# OmniSensor.net
KiCad netlist of a schematic drawn in Altium Designer
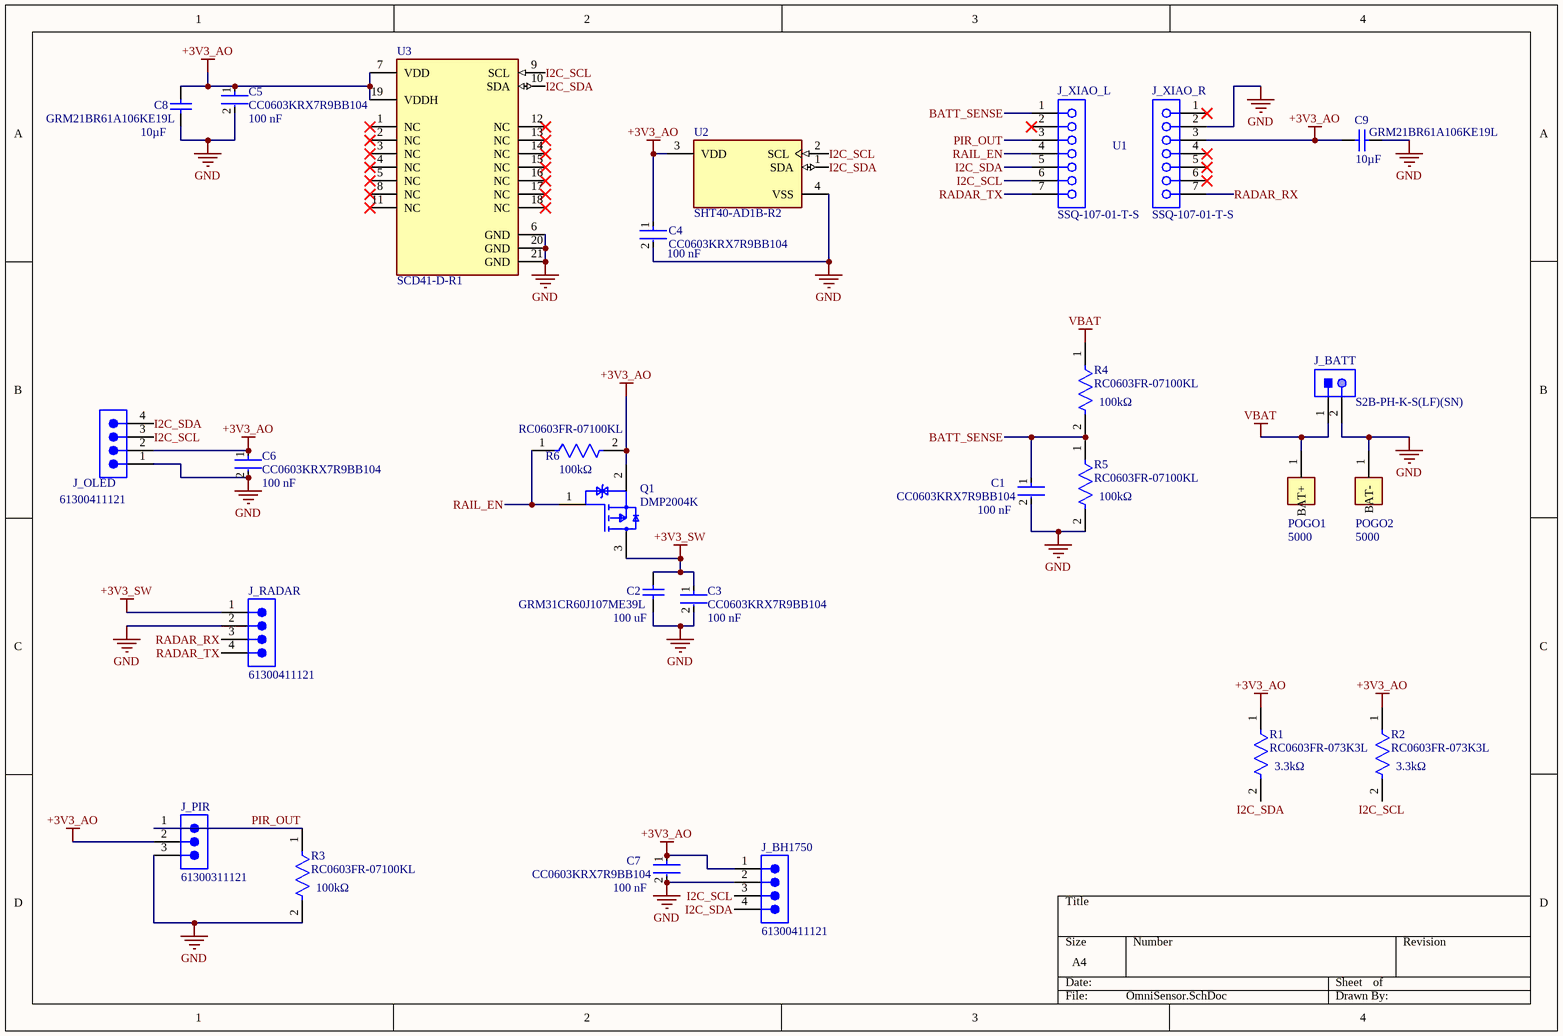
[diagram p0: OmniSensor.SchDoc]

(export (version "E")
  (design (tool "Eeschema 10.0.6"))
  (components
    (comp (ref "C1")
      (value "CC0603KRX7R9BB104")
      (footprint "FP-CC0603-DA-MFG")
      (description "CAP CER 0.1UF 50V X7R 0603")
      (fields
        (field (name "MANUFACTURER") "YAGEO")
        (field (name "VOLTAGE") "50 V")
        (field (name "ALTIUM_VALUE") "100 nF")
      )
      (libsource (lib "Altium Content Vault") (part "11868f565c42a9108669ba33697ecf6"))
    )
    (comp (ref "C2")
      (value "GRM31CR60J107ME39L")
      (footprint "CAPC3216X190X55ML30T25")
      (description "Chip Capacitor, 100 uF, +/- 20%, 6.3 V, -55 to 85 degC, 1206 (3216 Metric), RoHS, Tape and Reel")
      (fields (field (name "TOLERANCE") "20%") (field (name "CAPACITANCE") "100 uF"))
      (libsource (lib "Altium Content Vault") (part "CAP-NP-2"))
    )
    (comp (ref "C3")
      (value "CC0603KRX7R9BB104")
      (footprint "FP-CC0603-DA-MFG")
      (description "CAP CER 0.1UF 50V X7R 0603")
      (fields
        (field (name "MANUFACTURER") "YAGEO")
        (field (name "VOLTAGE") "50 V")
        (field (name "ALTIUM_VALUE") "100 nF")
      )
      (libsource (lib "Altium Content Vault") (part "11868f565c42a9108669ba33697ecf6"))
    )
    (comp (ref "C4")
      (value "CC0603KRX7R9BB104")
      (footprint "FP-CC0603-DA-MFG")
      (description "CAP CER 0.1UF 50V X7R 0603")
      (fields
        (field (name "MANUFACTURER") "YAGEO")
        (field (name "VOLTAGE") "50 V")
        (field (name "CAPACITANCE") "100 nF")
      )
      (libsource (lib "Altium Content Vault") (part "11868f565c42a9108669ba33697ecf6"))
    )
    (comp (ref "C5")
      (value "CC0603KRX7R9BB104")
      (footprint "FP-CC0603-DA-MFG")
      (description "CAP CER 0.1UF 50V X7R 0603")
      (fields
        (field (name "MANUFACTURER") "YAGEO")
        (field (name "VOLTAGE") "50 V")
        (field (name "CAPACITANCE") "100 nF")
      )
      (libsource (lib "Altium Content Vault") (part "11868f565c42a9108669ba33697ecf6"))
    )
    (comp (ref "C6")
      (value "CC0603KRX7R9BB104")
      (footprint "FP-CC0603-DA-MFG")
      (description "CAP CER 0.1UF 50V X7R 0603")
      (fields
        (field (name "MANUFACTURER") "YAGEO")
        (field (name "VOLTAGE") "50 V")
        (field (name "CAPACITANCE") "100 nF")
      )
      (libsource (lib "Altium Content Vault") (part "11868f565c42a9108669ba33697ecf6"))
    )
    (comp (ref "C7")
      (value "CC0603KRX7R9BB104")
      (footprint "FP-CC0603-DA-MFG")
      (description "CAP CER 0.1UF 50V X7R 0603")
      (fields
        (field (name "MANUFACTURER") "YAGEO")
        (field (name "VOLTAGE") "50 V")
        (field (name "CAPACITANCE") "100 nF")
      )
      (libsource (lib "Altium Content Vault") (part "11868f565c42a9108669ba33697ecf6"))
    )
    (comp (ref "C8")
      (value "GRM21BR61A106KE19L")
      (footprint "MURA-0805_H_1.35_M")
      (description "CAP, Ceramic, 10 uF, 10%, 10 V, 0805, RoHS, Tape and Reel")
      (fields
        (field (name "MANUFACTURER") "Murata")
        (field (name "TOLERANCE") "±10%")
        (field (name "CAPACITANCE") "10µF")
      )
      (libsource (lib "Altium Content Vault") (part "CAP-NP-2"))
    )
    (comp (ref "C9")
      (value "GRM21BR61A106KE19L")
      (footprint "MURA-0805_H_1.35_M")
      (description "CAP, Ceramic, 10 uF, 10%, 10 V, 0805, RoHS, Tape and Reel")
      (fields
        (field (name "MANUFACTURER") "Murata")
        (field (name "TOLERANCE") "±10%")
        (field (name "CAPACITANCE") "10µF")
      )
      (libsource (lib "Altium Content Vault") (part "CAP-NP-2"))
    )
    (comp (ref "J_BATT")
      (value "S2B-PH-K-S(LF)(SN)")
      (footprint "JST-S2B-PH-K-S_V")
      (fields (field (name "TOLERANCE") "20%"))
      (libsource (lib "Altium Content Vault") (part "CN-1P-M-R2"))
    )
    (comp (ref "J_BH1750")
      (value "61300411121")
      (footprint "61300411121")
      (description "THT Vertical Pin Header WR-PHD, Pitch 2.54 mm, Single Row, 4 pins")
      (libsource (lib "Altium Content Vault") (part "Header_Male_1R_04P"))
    )
    (comp (ref "J_OLED")
      (value "61300411121")
      (footprint "61300411121")
      (description "THT Vertical Pin Header WR-PHD, Pitch 2.54 mm, Single Row, 4 pins")
      (libsource (lib "Altium Content Vault") (part "Header_Male_1R_04P"))
    )
    (comp (ref "J_PIR")
      (value "61300311121")
      (footprint "61300311121")
      (description "THT Vertical Pin Header WR-PHD, Pitch 2.54 mm, Single Row, 3 pins")
      (libsource (lib "Altium Content Vault") (part "Header_Male_1R_03P"))
    )
    (comp (ref "J_RADAR")
      (value "61300411121")
      (footprint "61300411121")
      (description "THT Vertical Pin Header WR-PHD, Pitch 2.54 mm, Single Row, 4 pins")
      (libsource (lib "Altium Content Vault") (part "Header_Male_1R_04P"))
    )
    (comp (ref "J_XIAO_L")
      (value "SSQ-107-01-T-S")
      (footprint "SMTC-SSQ-107-01-X-S")
      (description "SQ Post Socket, Through-hole, Vertical, -55 to 105 degC, 2.54 mm Pitch, 7-Pin, Female, RoHS")
      (fields (field (name "MANUFACTURER") "Samtec"))
      (libsource (lib "Altium Content Vault") (part "SMTC-SSQ-107-01-X-S"))
    )
    (comp (ref "J_XIAO_R")
      (value "SSQ-107-01-T-S")
      (footprint "SMTC-SSQ-107-01-X-S")
      (description "SQ Post Socket, Through-hole, Vertical, -55 to 105 degC, 2.54 mm Pitch, 7-Pin, Female, RoHS")
      (fields (field (name "MANUFACTURER") "Samtec"))
      (libsource (lib "Altium Content Vault") (part "SMTC-SSQ-107-01-X-S"))
    )
    (comp (ref "POGO1")
      (value "5000")
      (footprint "FP-5000-MFG")
      (description "PC TEST POINT MINIATURE RED")
      (libsource (lib "Altium Content Vault") (part "1e4615820a309e3ce90f9e6d957b7fa"))
    )
    (comp (ref "POGO2")
      (value "5000")
      (footprint "FP-5000-MFG")
      (description "PC TEST POINT MINIATURE RED")
      (libsource (lib "Altium Content Vault") (part "1e4615820a309e3ce90f9e6d957b7fa"))
    )
    (comp (ref "Q1")
      (value "DMP2004K")
      (footprint "FP-SOT23-MFG")
      (description "MOSFET P-CH 20V 600MA SOT23-3")
      (fields
        (field (name "MANUFACTURER PART NUMBER") "DMP2004K-7")
        (field (name "OCTOPART") "https://octopart.com/dmp2004k-7-diodes+inc.-7151877")
      )
      (libsource (lib "Altium Content Vault") (part "0909edbb8d389a8e80b8543cd1a9d7a"))
    )
    (comp (ref "R1")
      (value "RC0603FR-073K3L")
      (footprint "FP-RC0603-0_55-MFG")
      (fields (field (name "TOLERANCE") "1%") (field (name "RESISTANCE") "3.3kΩ"))
      (libsource (lib "Altium Content Vault") (part "1029c3af85768c4190bb7ad29bc67b5"))
    )
    (comp (ref "R2")
      (value "RC0603FR-073K3L")
      (footprint "FP-RC0603-0_55-MFG")
      (fields (field (name "TOLERANCE") "1%") (field (name "RESISTANCE") "3.3kΩ"))
      (libsource (lib "Altium Content Vault") (part "1029c3af85768c4190bb7ad29bc67b5"))
    )
    (comp (ref "R3")
      (value "RC0603FR-07100KL")
      (footprint "FP-RC0603-0_55-MFG")
      (description "RES SMD 100K OHM 1% 1/10W 0603")
      (fields (field (name "RESISTANCE") "100kΩ") (field (name "TOLERANCE") "1%"))
      (libsource (lib "Altium Content Vault") (part "1029c3af85768c4190bb7ad29bc67b5"))
    )
    (comp (ref "R4")
      (value "RC0603FR-07100KL")
      (footprint "FP-RC0603-0_55-MFG")
      (description "RES SMD 100K OHM 1% 1/10W 0603")
      (fields (field (name "RESISTANCE") "100kΩ") (field (name "TOLERANCE") "1%"))
      (libsource (lib "Altium Content Vault") (part "1029c3af85768c4190bb7ad29bc67b5"))
    )
    (comp (ref "R5")
      (value "RC0603FR-07100KL")
      (footprint "FP-RC0603-0_55-MFG")
      (description "RES SMD 100K OHM 1% 1/10W 0603")
      (fields (field (name "RESISTANCE") "100kΩ") (field (name "TOLERANCE") "1%"))
      (libsource (lib "Altium Content Vault") (part "1029c3af85768c4190bb7ad29bc67b5"))
    )
    (comp (ref "R6")
      (value "RC0603FR-07100KL")
      (footprint "FP-RC0603-0_55-MFG")
      (description "RES SMD 100K OHM 1% 1/10W 0603")
      (fields (field (name "RESISTANCE") "100kΩ") (field (name "TOLERANCE") "1%"))
      (libsource (lib "Altium Content Vault") (part "1029c3af85768c4190bb7ad29bc67b5"))
    )
    (comp (ref "U2")
      (value "SHT40-AD1B-R2")
      (footprint "FP-SHT40-AD1B-R2-MFG")
      (description "SENSOR HUMIDITY 100 RH SMD")
      (libsource (lib "Altium Content Vault") (part "985d6b895d3abb4f56b1b691ea450a8"))
    )
    (comp (ref "U3")
      (value "SCD41-D-R1")
      (footprint "FP-SCD41-D-R1-MFG")
      (description "CO2 SENSOR 40 PPM I2C SMD")
      (libsource (lib "Altium Content Vault") (part "6ad75dfd843b95687531c15705827d7"))
    )
  )
  (nets
    (net (code "1") (name "+3V3_AO") (class "Default")
      (node (ref "C4") (pin "1") (pinfunction "1_1") (pintype "passive"))
      (node (ref "C5") (pin "1") (pinfunction "1_1") (pintype "passive"))
      (node (ref "C6") (pin "1") (pinfunction "1_1") (pintype "passive"))
      (node (ref "C7") (pin "1") (pinfunction "1_1") (pintype "passive"))
      (node (ref "C8") (pin "2") (pinfunction "2_2") (pintype "passive"))
      (node (ref "C9") (pin "1") (pinfunction "1_1") (pintype "passive"))
      (node (ref "J_BH1750") (pin "1") (pinfunction "1_1") (pintype "passive"))
      (node (ref "J_OLED") (pin "2") (pinfunction "2_2") (pintype "passive"))
      (node (ref "J_PIR") (pin "2") (pinfunction "2_2") (pintype "passive"))
      (node (ref "J_XIAO_R") (pin "3") (pinfunction "3_3") (pintype "passive"))
      (node (ref "Q1") (pin "2") (pinfunction "S_2") (pintype "passive"))
      (node (ref "R1") (pin "1") (pinfunction "1_1") (pintype "passive"))
      (node (ref "R2") (pin "1") (pinfunction "1_1") (pintype "passive"))
      (node (ref "R6") (pin "2") (pinfunction "2_2") (pintype "passive"))
      (node (ref "U2") (pin "3") (pinfunction "VDD_3") (pintype "power_in"))
      (node (ref "U3") (pin "19") (pinfunction "VDDH_19") (pintype "power_in"))
      (node (ref "U3") (pin "7") (pinfunction "VDD_7") (pintype "power_in"))
    )
    (net (code "2") (name "+3V3_SW") (class "Default")
      (node (ref "C2") (pin "2") (pinfunction "2_2") (pintype "passive"))
      (node (ref "C3") (pin "1") (pinfunction "1_1") (pintype "passive"))
      (node (ref "J_RADAR") (pin "1") (pinfunction "1_1") (pintype "passive"))
      (node (ref "Q1") (pin "3") (pinfunction "D_3") (pintype "passive"))
    )
    (net (code "3") (name "/BATT_SENSE") (class "Default")
      (node (ref "C1") (pin "1") (pinfunction "1_1") (pintype "passive"))
      (node (ref "J_XIAO_L") (pin "1") (pinfunction "1_1") (pintype "passive"))
      (node (ref "R4") (pin "2") (pinfunction "2_2") (pintype "passive"))
      (node (ref "R5") (pin "1") (pinfunction "1_1") (pintype "passive"))
    )
    (net (code "4") (name "/I2C_SCL") (class "Default")
      (node (ref "J_BH1750") (pin "3") (pinfunction "3_3") (pintype "passive"))
      (node (ref "J_OLED") (pin "3") (pinfunction "3_3") (pintype "passive"))
      (node (ref "J_XIAO_L") (pin "6") (pinfunction "6_6") (pintype "passive"))
      (node (ref "R2") (pin "2") (pinfunction "2_2") (pintype "passive"))
      (node (ref "U2") (pin "2") (pinfunction "SCL_2") (pintype "input"))
      (node (ref "U3") (pin "9") (pinfunction "SCL_9") (pintype "input"))
    )
    (net (code "5") (name "/I2C_SDA") (class "Default")
      (node (ref "J_BH1750") (pin "4") (pinfunction "4_4") (pintype "passive"))
      (node (ref "J_OLED") (pin "4") (pinfunction "4_4") (pintype "passive"))
      (node (ref "J_XIAO_L") (pin "5") (pinfunction "5_5") (pintype "passive"))
      (node (ref "R1") (pin "2") (pinfunction "2_2") (pintype "passive"))
      (node (ref "U2") (pin "1") (pinfunction "SDA_1") (pintype "bidirectional"))
      (node (ref "U3") (pin "10") (pinfunction "SDA_10") (pintype "bidirectional"))
    )
    (net (code "6") (name "/PIR_OUT") (class "Default")
      (node (ref "J_PIR") (pin "1") (pinfunction "1_1") (pintype "passive"))
      (node (ref "J_XIAO_L") (pin "3") (pinfunction "3_3") (pintype "passive"))
      (node (ref "R3") (pin "1") (pinfunction "1_1") (pintype "passive"))
    )
    (net (code "7") (name "/RADAR_RX") (class "Default")
      (node (ref "J_RADAR") (pin "3") (pinfunction "3_3") (pintype "passive"))
      (node (ref "J_XIAO_R") (pin "7") (pinfunction "7_7") (pintype "passive"))
    )
    (net (code "8") (name "/RADAR_TX") (class "Default")
      (node (ref "J_RADAR") (pin "4") (pinfunction "4_4") (pintype "passive"))
      (node (ref "J_XIAO_L") (pin "7") (pinfunction "7_7") (pintype "passive"))
    )
    (net (code "9") (name "/RAIL_EN") (class "Default")
      (node (ref "J_XIAO_L") (pin "4") (pinfunction "4_4") (pintype "passive"))
      (node (ref "Q1") (pin "1") (pinfunction "G_1") (pintype "passive"))
      (node (ref "R6") (pin "1") (pinfunction "1_1") (pintype "passive"))
    )
    (net (code "10") (name "GND") (class "Default")
      (node (ref "C1") (pin "2") (pinfunction "2_2") (pintype "passive"))
      (node (ref "C2") (pin "1") (pinfunction "1_1") (pintype "passive"))
      (node (ref "C3") (pin "2") (pinfunction "2_2") (pintype "passive"))
      (node (ref "C4") (pin "2") (pinfunction "2_2") (pintype "passive"))
      (node (ref "C5") (pin "2") (pinfunction "2_2") (pintype "passive"))
      (node (ref "C6") (pin "2") (pinfunction "2_2") (pintype "passive"))
      (node (ref "C7") (pin "2") (pinfunction "2_2") (pintype "passive"))
      (node (ref "C8") (pin "1") (pinfunction "1_1") (pintype "passive"))
      (node (ref "C9") (pin "2") (pinfunction "2_2") (pintype "passive"))
      (node (ref "J_BATT") (pin "2") (pinfunction "2_2") (pintype "passive"))
      (node (ref "J_BH1750") (pin "2") (pinfunction "2_2") (pintype "passive"))
      (node (ref "J_OLED") (pin "1") (pinfunction "1_1") (pintype "passive"))
      (node (ref "J_PIR") (pin "3") (pinfunction "3_3") (pintype "passive"))
      (node (ref "J_RADAR") (pin "2") (pinfunction "2_2") (pintype "passive"))
      (node (ref "J_XIAO_R") (pin "2") (pinfunction "2_2") (pintype "passive"))
      (node (ref "POGO2") (pin "1") (pinfunction "BAT-_1") (pintype "passive"))
      (node (ref "R3") (pin "2") (pinfunction "2_2") (pintype "passive"))
      (node (ref "R5") (pin "2") (pinfunction "2_2") (pintype "passive"))
      (node (ref "U2") (pin "4") (pinfunction "VSS_4") (pintype "power_in"))
      (node (ref "U3") (pin "20") (pinfunction "GND_20") (pintype "power_in"))
      (node (ref "U3") (pin "21") (pinfunction "GND_21") (pintype "power_in"))
      (node (ref "U3") (pin "6") (pinfunction "GND_6") (pintype "power_in"))
    )
    (net (code "11") (name "VBAT") (class "Default")
      (node (ref "J_BATT") (pin "1") (pinfunction "1_1") (pintype "passive"))
      (node (ref "POGO1") (pin "1") (pinfunction "BAT-_1") (pintype "passive"))
      (node (ref "R4") (pin "1") (pinfunction "1_1") (pintype "passive"))
    )
    (net (code "12") (name "unconnected-(J_XIAO_L-Pad2)") (class "Default")
      (node (ref "J_XIAO_L") (pin "2") (pinfunction "2_2") (pintype "passive+no_connect"))
    )
    (net (code "13") (name "unconnected-(J_XIAO_R-Pad1)") (class "Default")
      (node (ref "J_XIAO_R") (pin "1") (pinfunction "1_1") (pintype "passive+no_connect"))
    )
    (net (code "14") (name "unconnected-(J_XIAO_R-Pad4)") (class "Default")
      (node (ref "J_XIAO_R") (pin "4") (pinfunction "4_4") (pintype "passive+no_connect"))
    )
    (net (code "15") (name "unconnected-(J_XIAO_R-Pad5)") (class "Default")
      (node (ref "J_XIAO_R") (pin "5") (pinfunction "5_5") (pintype "passive+no_connect"))
    )
    (net (code "16") (name "unconnected-(J_XIAO_R-Pad6)") (class "Default")
      (node (ref "J_XIAO_R") (pin "6") (pinfunction "6_6") (pintype "passive+no_connect"))
    )
    (net (code "17") (name "unconnected-(U3-NC-Pad1)") (class "Default")
      (node (ref "U3") (pin "1") (pinfunction "NC_1") (pintype "passive+no_connect"))
    )
    (net (code "18") (name "unconnected-(U3-NC-Pad2)") (class "Default")
      (node (ref "U3") (pin "2") (pinfunction "NC_2") (pintype "passive+no_connect"))
    )
    (net (code "19") (name "unconnected-(U3-NC-Pad3)") (class "Default")
      (node (ref "U3") (pin "3") (pinfunction "NC_3") (pintype "passive+no_connect"))
    )
    (net (code "20") (name "unconnected-(U3-NC-Pad4)") (class "Default")
      (node (ref "U3") (pin "4") (pinfunction "NC_4") (pintype "passive+no_connect"))
    )
    (net (code "21") (name "unconnected-(U3-NC-Pad5)") (class "Default")
      (node (ref "U3") (pin "5") (pinfunction "NC_5") (pintype "passive+no_connect"))
    )
    (net (code "22") (name "unconnected-(U3-NC-Pad8)") (class "Default")
      (node (ref "U3") (pin "8") (pinfunction "NC_8") (pintype "passive+no_connect"))
    )
    (net (code "23") (name "unconnected-(U3-NC-Pad11)") (class "Default")
      (node (ref "U3") (pin "11") (pinfunction "NC_11") (pintype "passive+no_connect"))
    )
    (net (code "24") (name "unconnected-(U3-NC-Pad12)") (class "Default")
      (node (ref "U3") (pin "12") (pinfunction "NC_12") (pintype "passive+no_connect"))
    )
    (net (code "25") (name "unconnected-(U3-NC-Pad13)") (class "Default")
      (node (ref "U3") (pin "13") (pinfunction "NC_13") (pintype "passive+no_connect"))
    )
    (net (code "26") (name "unconnected-(U3-NC-Pad14)") (class "Default")
      (node (ref "U3") (pin "14") (pinfunction "NC_14") (pintype "passive+no_connect"))
    )
    (net (code "27") (name "unconnected-(U3-NC-Pad15)") (class "Default")
      (node (ref "U3") (pin "15") (pinfunction "NC_15") (pintype "passive+no_connect"))
    )
    (net (code "28") (name "unconnected-(U3-NC-Pad16)") (class "Default")
      (node (ref "U3") (pin "16") (pinfunction "NC_16") (pintype "passive+no_connect"))
    )
    (net (code "29") (name "unconnected-(U3-NC-Pad17)") (class "Default")
      (node (ref "U3") (pin "17") (pinfunction "NC_17") (pintype "passive+no_connect"))
    )
    (net (code "30") (name "unconnected-(U3-NC-Pad18)") (class "Default")
      (node (ref "U3") (pin "18") (pinfunction "NC_18") (pintype "passive+no_connect"))
    )
  )
)
